# P5c_Filter1B.net
KiCad netlist of a schematic drawn in Altium Designer
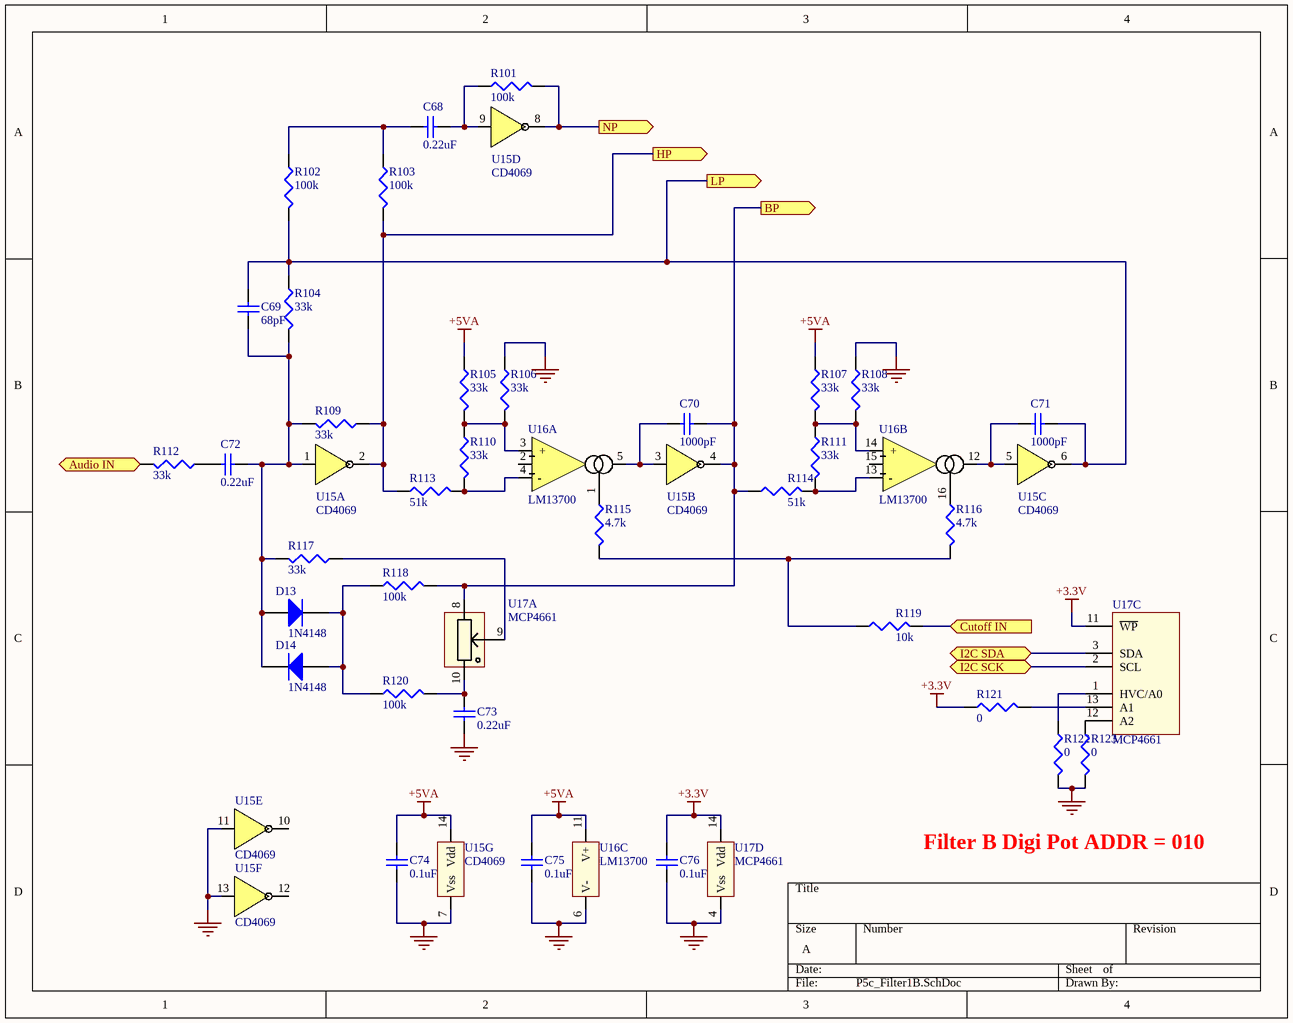
[diagram p0: P5c_Filter1B.SchDoc]

(export (version "E")
  (design (tool "Eeschema 10.0.6"))
  (components
    (comp (ref "C68")
      (value "0.22uF")
      (footprint "CAP 0603 (1608 metric)")
      (description "Capacitor (Semiconductor SIM Model)")
      (libsource (lib "Miscellaneous Devices") (part "Cap Semi"))
    )
    (comp (ref "C69")
      (value "68pF")
      (footprint "CAP 0603 (1608 metric)")
      (description "Capacitor (Semiconductor SIM Model)")
      (libsource (lib "Miscellaneous Devices") (part "Cap Semi"))
    )
    (comp (ref "C70")
      (value "1000pF")
      (footprint "CAP 0603 (1608 metric)")
      (description "Capacitor (Semiconductor SIM Model)")
      (libsource (lib "Miscellaneous Devices") (part "Cap Semi"))
    )
    (comp (ref "C71")
      (value "1000pF")
      (footprint "CAP 0603 (1608 metric)")
      (description "Capacitor (Semiconductor SIM Model)")
      (libsource (lib "Miscellaneous Devices") (part "Cap Semi"))
    )
    (comp (ref "C72")
      (value "0.22uF")
      (footprint "CAP 0603 (1608 metric)")
      (description "Capacitor (Semiconductor SIM Model)")
      (libsource (lib "Miscellaneous Devices") (part "Cap Semi"))
    )
    (comp (ref "C73")
      (value "0.22uF")
      (footprint "CAP 0603 (1608 metric)")
      (description "Capacitor (Semiconductor SIM Model)")
      (libsource (lib "Miscellaneous Devices") (part "Cap Semi"))
    )
    (comp (ref "C74")
      (value "0.1uF")
      (footprint "CAP 0603 (1608 metric)")
      (description "Capacitor (Semiconductor SIM Model)")
      (libsource (lib "Miscellaneous Devices") (part "Cap Semi"))
    )
    (comp (ref "C75")
      (value "0.1uF")
      (footprint "CAP 0603 (1608 metric)")
      (description "Capacitor (Semiconductor SIM Model)")
      (libsource (lib "Miscellaneous Devices") (part "Cap Semi"))
    )
    (comp (ref "C76")
      (value "0.1uF")
      (footprint "CAP 0603 (1608 metric)")
      (description "Capacitor (Semiconductor SIM Model)")
      (libsource (lib "Miscellaneous Devices") (part "Cap Semi"))
    )
    (comp (ref "D13")
      (value "1N4148")
      (description "High Conductance Fast Diode")
      (libsource (lib "Miscellaneous Devices") (part "Diode 1N4148"))
    )
    (comp (ref "D14")
      (value "1N4148")
      (description "High Conductance Fast Diode")
      (libsource (lib "Miscellaneous Devices") (part "Diode 1N4148"))
    )
    (comp (ref "R101")
      (value "100k")
      (footprint "RES 0603 (1608 metric)")
      (description "Resistor")
      (libsource (lib "Miscellaneous Devices") (part "Res3"))
    )
    (comp (ref "R102")
      (value "100k")
      (footprint "RES 0603 (1608 metric)")
      (description "Resistor")
      (libsource (lib "Miscellaneous Devices") (part "Res3"))
    )
    (comp (ref "R103")
      (value "100k")
      (footprint "RES 0603 (1608 metric)")
      (description "Resistor")
      (libsource (lib "Miscellaneous Devices") (part "Res3"))
    )
    (comp (ref "R104")
      (value "33k")
      (footprint "RES 0603 (1608 metric)")
      (description "Resistor")
      (libsource (lib "Miscellaneous Devices") (part "Res3"))
    )
    (comp (ref "R105")
      (value "33k")
      (footprint "RES 0603 (1608 metric)")
      (description "Resistor")
      (libsource (lib "Miscellaneous Devices") (part "Res3"))
    )
    (comp (ref "R106")
      (value "33k")
      (footprint "RES 0603 (1608 metric)")
      (description "Resistor")
      (libsource (lib "Miscellaneous Devices") (part "Res3"))
    )
    (comp (ref "R107")
      (value "33k")
      (footprint "RES 0603 (1608 metric)")
      (description "Resistor")
      (libsource (lib "Miscellaneous Devices") (part "Res3"))
    )
    (comp (ref "R108")
      (value "33k")
      (footprint "RES 0603 (1608 metric)")
      (description "Resistor")
      (libsource (lib "Miscellaneous Devices") (part "Res3"))
    )
    (comp (ref "R109")
      (value "33k")
      (footprint "RES 0603 (1608 metric)")
      (description "Resistor")
      (libsource (lib "Miscellaneous Devices") (part "Res3"))
    )
    (comp (ref "R110")
      (value "33k")
      (footprint "RES 0603 (1608 metric)")
      (description "Resistor")
      (libsource (lib "Miscellaneous Devices") (part "Res3"))
    )
    (comp (ref "R111")
      (value "33k")
      (footprint "RES 0603 (1608 metric)")
      (description "Resistor")
      (libsource (lib "Miscellaneous Devices") (part "Res3"))
    )
    (comp (ref "R112")
      (value "33k")
      (footprint "RES 0603 (1608 metric)")
      (description "Resistor")
      (libsource (lib "Miscellaneous Devices") (part "Res3"))
    )
    (comp (ref "R113")
      (value "51k")
      (footprint "RES 0603 (1608 metric)")
      (description "Resistor")
      (libsource (lib "Miscellaneous Devices") (part "Res3"))
    )
    (comp (ref "R114")
      (value "51k")
      (footprint "RES 0603 (1608 metric)")
      (description "Resistor")
      (libsource (lib "Miscellaneous Devices") (part "Res3"))
    )
    (comp (ref "R115")
      (value "4.7k")
      (footprint "RES 0603 (1608 metric)")
      (description "Resistor")
      (libsource (lib "Miscellaneous Devices") (part "Res3"))
    )
    (comp (ref "R116")
      (value "4.7k")
      (footprint "RES 0603 (1608 metric)")
      (description "Resistor")
      (libsource (lib "Miscellaneous Devices") (part "Res3"))
    )
    (comp (ref "R117")
      (value "33k")
      (footprint "RES 0603 (1608 metric)")
      (description "Resistor")
      (libsource (lib "Miscellaneous Devices") (part "Res3"))
    )
    (comp (ref "R118")
      (value "100k")
      (footprint "RES 0603 (1608 metric)")
      (description "Resistor")
      (libsource (lib "Miscellaneous Devices") (part "Res3"))
    )
    (comp (ref "R119")
      (value "10k")
      (footprint "RES 0603 (1608 metric)")
      (description "Resistor")
      (libsource (lib "Miscellaneous Devices") (part "Res3"))
    )
    (comp (ref "R120")
      (value "100k")
      (footprint "RES 0603 (1608 metric)")
      (description "Resistor")
      (libsource (lib "Miscellaneous Devices") (part "Res3"))
    )
    (comp (ref "R121")
      (value "0")
      (footprint "RES 0603 (1608 metric)")
      (description "Resistor")
      (libsource (lib "Miscellaneous Devices") (part "Res3"))
    )
    (comp (ref "R122")
      (value "0")
      (footprint "RES 0603 (1608 metric)")
      (description "Resistor")
      (libsource (lib "Miscellaneous Devices") (part "Res3"))
    )
    (comp (ref "R123")
      (value "0")
      (footprint "RES 0603 (1608 metric)")
      (description "Resistor")
      (libsource (lib "Miscellaneous Devices") (part "Res3"))
    )
    (comp (ref "U15")
      (value "CD4069")
      (description "Hex Inverter")
      (libsource (lib "FilterPoC") (part "CD4069"))
    )
    (comp (ref "U16")
      (value "LM13700")
      (description "Dual Transconductance OpAmp")
      (libsource (lib "") (part "LM13700M_2"))
    )
    (comp (ref "U17")
      (value "MCP4661")
      (description "Dual DigiPot non volatile I2C")
      (libsource (lib "FilterPoC") (part "MCP4661"))
    )
  )
  (nets
    (net (code "1") (name "+3.3V") (class "Default")
      (node (ref "C76") (pin "1") (pinfunction "1_1") (pintype "passive"))
      (node (ref "R121") (pin "1") (pinfunction "1_1") (pintype "passive"))
      (node (ref "U17") (pin "11") (pinfunction "~{WP}_11") (pintype "passive"))
      (node (ref "U17") (pin "14") (pinfunction "Vdd_14") (pintype "power_in"))
    )
    (net (code "2") (name "+5VA") (class "Default")
      (node (ref "C74") (pin "1") (pinfunction "1_1") (pintype "passive"))
      (node (ref "C75") (pin "1") (pinfunction "1_1") (pintype "passive"))
      (node (ref "R105") (pin "1") (pinfunction "1_1") (pintype "passive"))
      (node (ref "R107") (pin "1") (pinfunction "1_1") (pintype "passive"))
      (node (ref "U15") (pin "14") (pinfunction "Vdd_14") (pintype "power_in"))
      (node (ref "U16") (pin "11") (pinfunction "V+_11") (pintype "power_in"))
    )
    (net (code "3") (name "/Audio IN") (class "Default")
      (node (ref "R112") (pin "2") (pinfunction "2_2") (pintype "passive"))
    )
    (net (code "4") (name "/BP") (class "Default")
      (node (ref "C70") (pin "2") (pinfunction "2_2") (pintype "passive"))
      (node (ref "R114") (pin "1") (pinfunction "1_1") (pintype "passive"))
      (node (ref "R118") (pin "2") (pinfunction "2_2") (pintype "passive"))
      (node (ref "U15") (pin "4") (pinfunction "~{B}_4") (pintype "passive"))
      (node (ref "U17") (pin "8") (pinfunction "P0A_8") (pintype "passive"))
    )
    (net (code "5") (name "/Cutoff IN") (class "Default")
      (node (ref "R119") (pin "2") (pinfunction "2_2") (pintype "passive"))
    )
    (net (code "6") (name "/HP") (class "Default")
      (node (ref "R103") (pin "2") (pinfunction "2_2") (pintype "passive"))
      (node (ref "R109") (pin "1") (pinfunction "1_1") (pintype "passive"))
      (node (ref "R113") (pin "1") (pinfunction "1_1") (pintype "passive"))
      (node (ref "U15") (pin "2") (pinfunction "~{A}_2") (pintype "passive"))
    )
    (net (code "7") (name "/I2C SCK") (class "Default")
      (node (ref "U17") (pin "2") (pinfunction "SCL_2") (pintype "passive"))
    )
    (net (code "8") (name "/I2C SDA") (class "Default")
      (node (ref "U17") (pin "3") (pinfunction "SDA_3") (pintype "passive"))
    )
    (net (code "9") (name "/LP") (class "Default")
      (node (ref "C69") (pin "2") (pinfunction "2_2") (pintype "passive"))
      (node (ref "C71") (pin "2") (pinfunction "2_2") (pintype "passive"))
      (node (ref "R102") (pin "2") (pinfunction "2_2") (pintype "passive"))
      (node (ref "R104") (pin "1") (pinfunction "1_1") (pintype "passive"))
      (node (ref "U15") (pin "6") (pinfunction "~{C}_6") (pintype "passive"))
    )
    (net (code "10") (name "/NP") (class "Default")
      (node (ref "R101") (pin "2") (pinfunction "2_2") (pintype "passive"))
      (node (ref "U15") (pin "8") (pinfunction "~{D}_8") (pintype "passive"))
    )
    (net (code "11") (name "GND") (class "Default")
      (node (ref "C73") (pin "2") (pinfunction "2_2") (pintype "passive"))
      (node (ref "C74") (pin "2") (pinfunction "2_2") (pintype "passive"))
      (node (ref "C75") (pin "2") (pinfunction "2_2") (pintype "passive"))
      (node (ref "C76") (pin "2") (pinfunction "2_2") (pintype "passive"))
      (node (ref "R106") (pin "1") (pinfunction "1_1") (pintype "passive"))
      (node (ref "R108") (pin "1") (pinfunction "1_1") (pintype "passive"))
      (node (ref "R122") (pin "2") (pinfunction "2_2") (pintype "passive"))
      (node (ref "R123") (pin "2") (pinfunction "2_2") (pintype "passive"))
      (node (ref "U15") (pin "11") (pinfunction "E_11") (pintype "passive"))
      (node (ref "U15") (pin "13") (pinfunction "F_13") (pintype "passive"))
      (node (ref "U15") (pin "7") (pinfunction "Vss_7") (pintype "power_in"))
      (node (ref "U16") (pin "6") (pinfunction "V-_6") (pintype "power_in"))
      (node (ref "U17") (pin "4") (pinfunction "Vss_4") (pintype "power_in"))
    )
    (net (code "12") (name "Net-(C68-Pad1)") (class "Default")
      (node (ref "C68") (pin "1") (pinfunction "1_1") (pintype "passive"))
      (node (ref "R102") (pin "1") (pinfunction "1_1") (pintype "passive"))
      (node (ref "R103") (pin "1") (pinfunction "1_1") (pintype "passive"))
    )
    (net (code "13") (name "Net-(C72-Pad1)") (class "Default")
      (node (ref "C72") (pin "1") (pinfunction "1_1") (pintype "passive"))
      (node (ref "R112") (pin "1") (pinfunction "1_1") (pintype "passive"))
    )
    (net (code "14") (name "Net-(D13-A)") (class "Default")
      (node (ref "C69") (pin "1") (pinfunction "1_1") (pintype "passive"))
      (node (ref "C72") (pin "2") (pinfunction "2_2") (pintype "passive"))
      (node (ref "D13") (pin "1") (pinfunction "A_1") (pintype "passive"))
      (node (ref "D14") (pin "2") (pinfunction "K_2") (pintype "passive"))
      (node (ref "R104") (pin "2") (pinfunction "2_2") (pintype "passive"))
      (node (ref "R109") (pin "2") (pinfunction "2_2") (pintype "passive"))
      (node (ref "R117") (pin "2") (pinfunction "2_2") (pintype "passive"))
      (node (ref "U15") (pin "1") (pinfunction "A_1") (pintype "passive"))
    )
    (net (code "15") (name "Net-(D13-K)") (class "Default")
      (node (ref "D13") (pin "2") (pinfunction "K_2") (pintype "passive"))
      (node (ref "D14") (pin "1") (pinfunction "A_1") (pintype "passive"))
      (node (ref "R118") (pin "1") (pinfunction "1_1") (pintype "passive"))
      (node (ref "R120") (pin "1") (pinfunction "1_1") (pintype "passive"))
    )
    (net (code "16") (name "Net-(R115-Pad2)") (class "Default")
      (node (ref "R115") (pin "2") (pinfunction "2_2") (pintype "passive"))
      (node (ref "R116") (pin "2") (pinfunction "2_2") (pintype "passive"))
      (node (ref "R119") (pin "1") (pinfunction "1_1") (pintype "passive"))
    )
    (net (code "17") (name "Net-(U15B-B)") (class "Default")
      (node (ref "C70") (pin "1") (pinfunction "1_1") (pintype "passive"))
      (node (ref "U15") (pin "3") (pinfunction "B_3") (pintype "passive"))
      (node (ref "U16") (pin "5") (pinfunction "OUT_5") (pintype "passive"))
    )
    (net (code "18") (name "Net-(U15C-C)") (class "Default")
      (node (ref "C71") (pin "1") (pinfunction "1_1") (pintype "passive"))
      (node (ref "U15") (pin "5") (pinfunction "C_5") (pintype "passive"))
      (node (ref "U16") (pin "12") (pinfunction "OUT_12") (pintype "passive"))
    )
    (net (code "19") (name "Net-(U15D-D)") (class "Default")
      (node (ref "C68") (pin "2") (pinfunction "2_2") (pintype "passive"))
      (node (ref "R101") (pin "1") (pinfunction "1_1") (pintype "passive"))
      (node (ref "U15") (pin "9") (pinfunction "D_9") (pintype "passive"))
    )
    (net (code "20") (name "Net-(U16A-+)") (class "Default")
      (node (ref "R105") (pin "2") (pinfunction "2_2") (pintype "passive"))
      (node (ref "R106") (pin "2") (pinfunction "2_2") (pintype "passive"))
      (node (ref "R110") (pin "1") (pinfunction "1_1") (pintype "passive"))
      (node (ref "U16") (pin "3") (pinfunction "+_3") (pintype "passive"))
    )
    (net (code "21") (name "Net-(U16A--)") (class "Default")
      (node (ref "R110") (pin "2") (pinfunction "2_2") (pintype "passive"))
      (node (ref "R113") (pin "2") (pinfunction "2_2") (pintype "passive"))
      (node (ref "U16") (pin "4") (pinfunction "-_4") (pintype "passive"))
    )
    (net (code "22") (name "Net-(U16A-BIAS)") (class "Default")
      (node (ref "R115") (pin "1") (pinfunction "1_1") (pintype "passive"))
      (node (ref "U16") (pin "1") (pinfunction "BIAS_1") (pintype "passive"))
    )
    (net (code "23") (name "Net-(U16B-+)") (class "Default")
      (node (ref "R107") (pin "2") (pinfunction "2_2") (pintype "passive"))
      (node (ref "R108") (pin "2") (pinfunction "2_2") (pintype "passive"))
      (node (ref "R111") (pin "1") (pinfunction "1_1") (pintype "passive"))
      (node (ref "U16") (pin "14") (pinfunction "+_14") (pintype "passive"))
    )
    (net (code "24") (name "Net-(U16B--)") (class "Default")
      (node (ref "R111") (pin "2") (pinfunction "2_2") (pintype "passive"))
      (node (ref "R114") (pin "2") (pinfunction "2_2") (pintype "passive"))
      (node (ref "U16") (pin "13") (pinfunction "-_13") (pintype "passive"))
    )
    (net (code "25") (name "Net-(U16B-BIAS)") (class "Default")
      (node (ref "R116") (pin "1") (pinfunction "1_1") (pintype "passive"))
      (node (ref "U16") (pin "16") (pinfunction "BIAS_16") (pintype "passive"))
    )
    (net (code "26") (name "Net-(U17A-P0B)") (class "Default")
      (node (ref "C73") (pin "1") (pinfunction "1_1") (pintype "passive"))
      (node (ref "R120") (pin "2") (pinfunction "2_2") (pintype "passive"))
      (node (ref "U17") (pin "10") (pinfunction "P0B_10") (pintype "passive"))
    )
    (net (code "27") (name "Net-(U17A-P0W)") (class "Default")
      (node (ref "R117") (pin "1") (pinfunction "1_1") (pintype "passive"))
      (node (ref "U17") (pin "9") (pinfunction "P0W_9") (pintype "passive"))
    )
    (net (code "28") (name "Net-(U17C-A1)") (class "Default")
      (node (ref "R121") (pin "2") (pinfunction "2_2") (pintype "passive"))
      (node (ref "U17") (pin "13") (pinfunction "A1_13") (pintype "power_in"))
    )
    (net (code "29") (name "Net-(U17C-A2)") (class "Default")
      (node (ref "R123") (pin "1") (pinfunction "1_1") (pintype "passive"))
      (node (ref "U17") (pin "12") (pinfunction "A2_12") (pintype "power_in"))
    )
    (net (code "30") (name "Net-(U17C-HVC{slash}A0)") (class "Default")
      (node (ref "R122") (pin "1") (pinfunction "1_1") (pintype "passive"))
      (node (ref "U17") (pin "1") (pinfunction "HVC/A0_1") (pintype "power_in"))
    )
    (net (code "31") (name "unconnected-(U15E-~{E}-Pad10)") (class "Default")
      (node (ref "U15") (pin "10") (pinfunction "~{E}_10") (pintype "passive"))
    )
    (net (code "32") (name "unconnected-(U15F-~{F}-Pad12)") (class "Default")
      (node (ref "U15") (pin "12") (pinfunction "~{F}_12") (pintype "passive"))
    )
    (net (code "33") (name "unconnected-(U16A-Diode_BIAS-Pad2)") (class "Default")
      (node (ref "U16") (pin "2") (pinfunction "Diode_BIAS_2") (pintype "passive"))
    )
    (net (code "34") (name "unconnected-(U16B-Diode_BIAS-Pad15)") (class "Default")
      (node (ref "U16") (pin "15") (pinfunction "Diode_BIAS_15") (pintype "passive"))
    )
  )
)
